# LazeMWC.net
KiCad netlist of a schematic drawn in Altium Designer
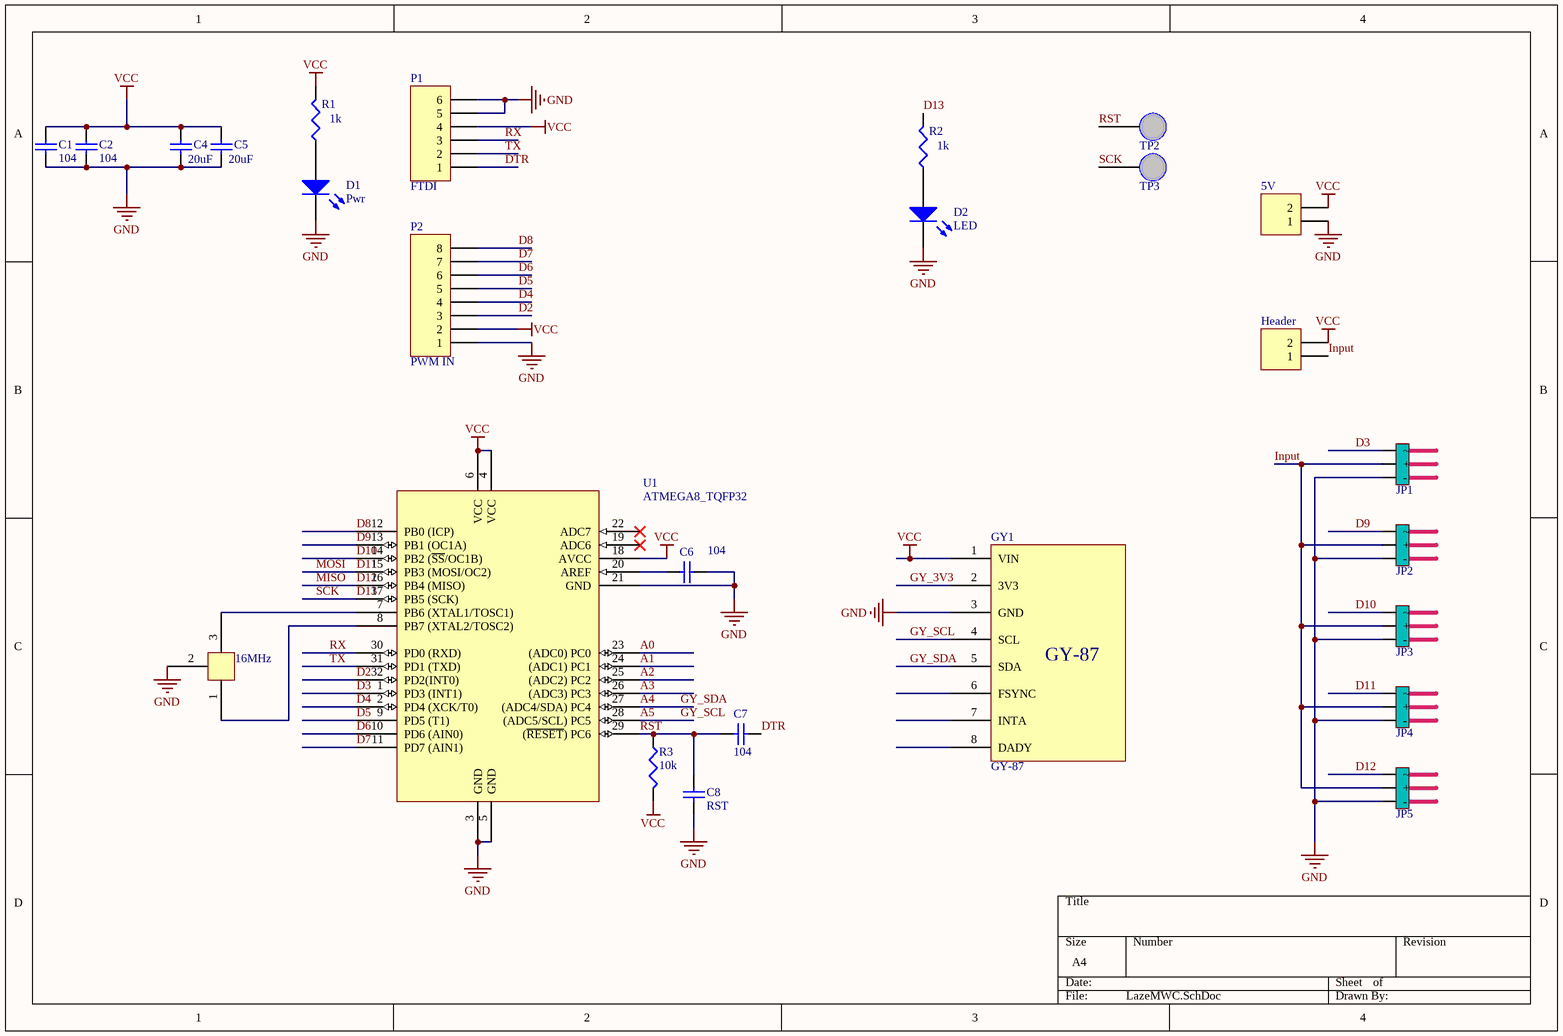
[diagram p0: LazeMWC.SchDoc]

(export (version "E")
  (design (tool "Eeschema 10.0.6"))
  (components
    (comp (ref "5V")
      (value "Header 2")
      (footprint "HDR1X2")
      (description "Header, 2-Pin")
      (fields (field (name "PUBLISHER") "Altium Limited"))
      (libsource (lib "Miscellaneous Connectors") (part "Header 2"))
    )
    (comp (ref "C1")
      (value "104")
      (footprint "CAPC1608L")
      (description "Capacitor (Semiconductor SIM Model)")
      (fields (field (name "PUBLISHER") "Altium Limited"))
      (libsource (lib "Miscellaneous Devices") (part "Cap Semi"))
    )
    (comp (ref "C2")
      (value "104")
      (footprint "CAPC1608L")
      (description "Capacitor (Semiconductor SIM Model)")
      (fields (field (name "PUBLISHER") "Altium Limited"))
      (libsource (lib "Miscellaneous Devices") (part "Cap Semi"))
    )
    (comp (ref "C4")
      (value "20uF")
      (footprint "CAPC3216L")
      (description "Capacitor (Semiconductor SIM Model)")
      (fields (field (name "PUBLISHER") "Altium Limited"))
      (libsource (lib "Miscellaneous Devices") (part "Cap Semi"))
    )
    (comp (ref "C5")
      (value "20uF")
      (footprint "CAPC3216L")
      (description "Capacitor (Semiconductor SIM Model)")
      (fields (field (name "PUBLISHER") "Altium Limited"))
      (libsource (lib "Miscellaneous Devices") (part "Cap Semi"))
    )
    (comp (ref "C6")
      (value "104")
      (footprint "CAPC1608L")
      (description "Capacitor (Semiconductor SIM Model)")
      (fields (field (name "PUBLISHER") "Altium Limited"))
      (libsource (lib "Miscellaneous Devices") (part "Cap Semi"))
    )
    (comp (ref "C7")
      (value "104")
      (footprint "CAPC1608L")
      (description "Capacitor (Semiconductor SIM Model)")
      (fields (field (name "PUBLISHER") "Altium Limited"))
      (libsource (lib "Miscellaneous Devices") (part "Cap Semi"))
    )
    (comp (ref "C8")
      (value "RST")
      (footprint "CAPC1608L")
      (description "Capacitor (Semiconductor SIM Model)")
      (fields (field (name "PUBLISHER") "Altium Limited"))
      (libsource (lib "Miscellaneous Devices") (part "Cap Semi"))
    )
    (comp (ref "Crystal1")
      (value "16MHz")
      (footprint "Crystal3Foot")
      (libsource (lib "Drone") (part "Crystal3Foot"))
    )
    (comp (ref "D1")
      (value "Pwr")
      (footprint "CAPC2012L")
      (description "Typical RED, GREEN, YELLOW, AMBER GaAs LED")
      (fields (field (name "PUBLISHER") "Altium Limited"))
      (libsource (lib "Miscellaneous Devices") (part "LED2"))
    )
    (comp (ref "D2")
      (value "LED")
      (footprint "CAPC2012L")
      (description "Typical RED, GREEN, YELLOW, AMBER GaAs LED")
      (fields (field (name "PUBLISHER") "Altium Limited"))
      (libsource (lib "Miscellaneous Devices") (part "LED2"))
    )
    (comp (ref "GY1") (value "GY-87") (footprint "GY-87") (libsource (lib "Drone") (part "GY-87")))
    (comp (ref "Header")
      (value "Header 2")
      (footprint "HDR1X2")
      (description "Header, 2-Pin")
      (fields (field (name "PUBLISHER") "Altium Limited"))
      (libsource (lib "Miscellaneous Connectors") (part "Header 2"))
    )
    (comp (ref "JP1")
      (value "Servo out 1")
      (footprint "JP")
      (description "Header, 3-Pin, 0.1\"")
      (fields (field (name "MANUFACTURER") "Generic Components"))
      (libsource (lib "Drone") (part "Hdr 3 Pin 0.1"))
    )
    (comp (ref "JP2")
      (value "Servo out 1")
      (footprint "JP")
      (description "Header, 3-Pin, 0.1\"")
      (fields (field (name "MANUFACTURER") "Generic Components"))
      (libsource (lib "Drone") (part "Hdr 3 Pin 0.1"))
    )
    (comp (ref "JP3")
      (value "Servo out 1")
      (footprint "JP")
      (description "Header, 3-Pin, 0.1\"")
      (fields (field (name "MANUFACTURER") "Generic Components"))
      (libsource (lib "Drone") (part "Hdr 3 Pin 0.1"))
    )
    (comp (ref "JP4")
      (value "Servo out 1")
      (footprint "JP")
      (description "Header, 3-Pin, 0.1\"")
      (fields (field (name "MANUFACTURER") "Generic Components"))
      (libsource (lib "Drone") (part "Hdr 3 Pin 0.1"))
    )
    (comp (ref "JP5")
      (value "Servo out 1")
      (footprint "JP")
      (description "Header, 3-Pin, 0.1\"")
      (fields (field (name "MANUFACTURER") "Generic Components"))
      (libsource (lib "Drone") (part "Hdr 3 Pin 0.1"))
    )
    (comp (ref "P1")
      (value "FTDI")
      (footprint "HDR1X6")
      (description "Header, 6-Pin")
      (fields (field (name "PUBLISHER") "Altium Limited"))
      (libsource (lib "Miscellaneous Connectors") (part "Header 6"))
    )
    (comp (ref "P2")
      (value "PWM IN")
      (footprint "HDR1X8")
      (description "Header, 8-Pin")
      (fields (field (name "PUBLISHER") "Altium Limited"))
      (libsource (lib "Miscellaneous Connectors") (part "Header 8"))
    )
    (comp (ref "R1")
      (value "1k")
      (footprint "RESC1608L")
      (description "Resistor")
      (fields (field (name "PUBLISHER") "Altium Limited"))
      (libsource (lib "Miscellaneous Devices") (part "Res3"))
    )
    (comp (ref "R2")
      (value "1k")
      (footprint "RESC1608L")
      (description "Resistor")
      (fields (field (name "PUBLISHER") "Altium Limited"))
      (libsource (lib "Miscellaneous Devices") (part "Res3"))
    )
    (comp (ref "R3")
      (value "10k")
      (footprint "RESC1608L")
      (description "Resistor")
      (fields (field (name "PUBLISHER") "Altium Limited"))
      (libsource (lib "Miscellaneous Devices") (part "Res3"))
    )
    (comp (ref "TP2") (value "Test Pad") (footprint "Test Pad") (libsource (lib "Drone") (part "Test Pad")))
    (comp (ref "TP3") (value "Test Pad") (footprint "Test Pad") (libsource (lib "Drone") (part "Test Pad")))
    (comp (ref "U1")
      (value "ATMEGA8_TQFP32")
      (footprint "atmega328fix")
      (description "Atmel Microcontroller - Library created by carel..  <www.mpfreezone.com>")
      (libsource (lib "Drone") (part "ATMEGA8_TQFP32"))
    )
  )
  (nets
    (net (code "1") (name "/A0") (class "Default")
      (node (ref "U1") (pin "23") (pinfunction "(ADC0)_PC0_23") (pintype "bidirectional"))
    )
    (net (code "2") (name "/A1") (class "Default")
      (node (ref "U1") (pin "24") (pinfunction "(ADC1)_PC1_24") (pintype "bidirectional"))
    )
    (net (code "3") (name "/A2") (class "Default")
      (node (ref "U1") (pin "25") (pinfunction "(ADC2)_PC2_25") (pintype "bidirectional"))
    )
    (net (code "4") (name "/A3") (class "Default")
      (node (ref "U1") (pin "26") (pinfunction "(ADC3)_PC3_26") (pintype "bidirectional"))
    )
    (net (code "5") (name "/A4") (class "Default")
      (node (ref "GY1") (pin "5") (pinfunction "SDA_5") (pintype "passive"))
      (node (ref "U1") (pin "27") (pinfunction "(ADC4/SDA)_PC4_27") (pintype "bidirectional"))
    )
    (net (code "6") (name "/A5") (class "Default")
      (node (ref "GY1") (pin "4") (pinfunction "SCL_4") (pintype "passive"))
      (node (ref "U1") (pin "28") (pinfunction "(ADC5/SCL)_PC5_28") (pintype "bidirectional"))
    )
    (net (code "7") (name "/D2") (class "Default")
      (node (ref "P2") (pin "3") (pinfunction "3_3") (pintype "passive"))
      (node (ref "U1") (pin "32") (pinfunction "PD2(INT0)_32") (pintype "bidirectional"))
    )
    (net (code "8") (name "/D3") (class "Default")
      (node (ref "JP1") (pin "1") (pinfunction "~_1") (pintype "passive"))
      (node (ref "U1") (pin "1") (pinfunction "PD3_(INT1)_1") (pintype "bidirectional"))
    )
    (net (code "9") (name "/D4") (class "Default")
      (node (ref "P2") (pin "4") (pinfunction "4_4") (pintype "passive"))
      (node (ref "U1") (pin "2") (pinfunction "PD4_(XCK/T0)_2") (pintype "bidirectional"))
    )
    (net (code "10") (name "/D5") (class "Default")
      (node (ref "P2") (pin "5") (pinfunction "5_5") (pintype "passive"))
      (node (ref "U1") (pin "9") (pinfunction "PD5_(T1)_9") (pintype "passive"))
    )
    (net (code "11") (name "/D6") (class "Default")
      (node (ref "P2") (pin "6") (pinfunction "6_6") (pintype "passive"))
      (node (ref "U1") (pin "10") (pinfunction "PD6_(AIN0)_10") (pintype "passive"))
    )
    (net (code "12") (name "/D7") (class "Default")
      (node (ref "P2") (pin "7") (pinfunction "7_7") (pintype "passive"))
      (node (ref "U1") (pin "11") (pinfunction "PD7_(AIN1)_11") (pintype "passive"))
    )
    (net (code "13") (name "/D8") (class "Default")
      (node (ref "P2") (pin "8") (pinfunction "8_8") (pintype "passive"))
      (node (ref "U1") (pin "12") (pinfunction "PB0_(ICP)_12") (pintype "passive"))
    )
    (net (code "14") (name "/D9") (class "Default")
      (node (ref "JP2") (pin "1") (pinfunction "~_1") (pintype "passive"))
      (node (ref "U1") (pin "13") (pinfunction "PB1_(OC1A)_13") (pintype "bidirectional"))
    )
    (net (code "15") (name "/D10") (class "Default")
      (node (ref "JP3") (pin "1") (pinfunction "~_1") (pintype "passive"))
      (node (ref "U1") (pin "14") (pinfunction "PB2_(~{SS}/OC1B)_14") (pintype "bidirectional"))
    )
    (net (code "16") (name "/D11") (class "Default")
      (node (ref "JP4") (pin "1") (pinfunction "~_1") (pintype "passive"))
      (node (ref "U1") (pin "15") (pinfunction "PB3_(MOSI/OC2)_15") (pintype "bidirectional"))
    )
    (net (code "17") (name "/D12") (class "Default")
      (node (ref "JP5") (pin "1") (pinfunction "~_1") (pintype "passive"))
      (node (ref "U1") (pin "16") (pinfunction "PB4_(MISO)_16") (pintype "bidirectional"))
    )
    (net (code "18") (name "/D13") (class "Default")
      (node (ref "R2") (pin "2") (pinfunction "2_2") (pintype "passive"))
      (node (ref "TP3") (pin "1") (pinfunction "1_1") (pintype "passive"))
      (node (ref "U1") (pin "17") (pinfunction "PB5_(SCK)_17") (pintype "bidirectional"))
    )
    (net (code "19") (name "/DTR") (class "Default")
      (node (ref "C7") (pin "2") (pinfunction "2_2") (pintype "passive"))
      (node (ref "P1") (pin "1") (pinfunction "1_1") (pintype "passive"))
    )
    (net (code "20") (name "/GY_3V3") (class "Default")
      (node (ref "GY1") (pin "2") (pinfunction "3V3_2") (pintype "passive"))
    )
    (net (code "21") (name "/Input") (class "Default")
      (node (ref "Header") (pin "1") (pinfunction "1_1") (pintype "passive"))
      (node (ref "JP1") (pin "2") (pinfunction "+_2") (pintype "passive"))
      (node (ref "JP2") (pin "2") (pinfunction "+_2") (pintype "passive"))
      (node (ref "JP3") (pin "2") (pinfunction "+_2") (pintype "passive"))
      (node (ref "JP4") (pin "2") (pinfunction "+_2") (pintype "passive"))
      (node (ref "JP5") (pin "2") (pinfunction "+_2") (pintype "passive"))
    )
    (net (code "22") (name "/RST") (class "Default")
      (node (ref "C7") (pin "1") (pinfunction "1_1") (pintype "passive"))
      (node (ref "C8") (pin "2") (pinfunction "2_2") (pintype "passive"))
      (node (ref "R3") (pin "1") (pinfunction "1_1") (pintype "passive"))
      (node (ref "TP2") (pin "1") (pinfunction "1_1") (pintype "passive"))
      (node (ref "U1") (pin "29") (pinfunction "(~{RESET})_PC6_29") (pintype "bidirectional"))
    )
    (net (code "23") (name "/RX") (class "Default")
      (node (ref "P1") (pin "3") (pinfunction "3_3") (pintype "passive"))
      (node (ref "U1") (pin "30") (pinfunction "PD0_(RXD)_30") (pintype "bidirectional"))
    )
    (net (code "24") (name "/TX") (class "Default")
      (node (ref "P1") (pin "2") (pinfunction "2_2") (pintype "passive"))
      (node (ref "U1") (pin "31") (pinfunction "PD1_(TXD)_31") (pintype "bidirectional"))
    )
    (net (code "25") (name "GND") (class "Default")
      (node (ref "5V") (pin "1") (pinfunction "1_1") (pintype "passive"))
      (node (ref "C1") (pin "1") (pinfunction "1_1") (pintype "passive"))
      (node (ref "C2") (pin "1") (pinfunction "1_1") (pintype "passive"))
      (node (ref "C4") (pin "1") (pinfunction "1_1") (pintype "passive"))
      (node (ref "C5") (pin "1") (pinfunction "1_1") (pintype "passive"))
      (node (ref "C6") (pin "2") (pinfunction "2_2") (pintype "passive"))
      (node (ref "C8") (pin "1") (pinfunction "1_1") (pintype "passive"))
      (node (ref "Crystal1") (pin "2") (pinfunction "2_2") (pintype "passive"))
      (node (ref "D1") (pin "2") (pinfunction "K_2") (pintype "passive"))
      (node (ref "D2") (pin "2") (pinfunction "K_2") (pintype "passive"))
      (node (ref "GY1") (pin "3") (pinfunction "GND_3") (pintype "passive"))
      (node (ref "JP1") (pin "3") (pinfunction "-_3") (pintype "passive"))
      (node (ref "JP2") (pin "3") (pinfunction "-_3") (pintype "passive"))
      (node (ref "JP3") (pin "3") (pinfunction "-_3") (pintype "passive"))
      (node (ref "JP4") (pin "3") (pinfunction "-_3") (pintype "passive"))
      (node (ref "JP5") (pin "3") (pinfunction "-_3") (pintype "passive"))
      (node (ref "P1") (pin "5") (pinfunction "5_5") (pintype "passive"))
      (node (ref "P1") (pin "6") (pinfunction "6_6") (pintype "passive"))
      (node (ref "P2") (pin "1") (pinfunction "1_1") (pintype "passive"))
      (node (ref "U1") (pin "21") (pinfunction "GND_21") (pintype "passive"))
      (node (ref "U1") (pin "3") (pinfunction "GND_3") (pintype "passive"))
      (node (ref "U1") (pin "5") (pinfunction "GND_5") (pintype "power_in"))
    )
    (net (code "26") (name "Net-(Crystal1-0)") (class "Default")
      (node (ref "Crystal1") (pin "1") (pinfunction "0_1") (pintype "passive"))
      (node (ref "U1") (pin "8") (pinfunction "PB7_(XTAL2/TOSC2)_8") (pintype "passive"))
    )
    (net (code "27") (name "Net-(Crystal1-1)") (class "Default")
      (node (ref "Crystal1") (pin "3") (pinfunction "1_3") (pintype "passive"))
      (node (ref "U1") (pin "7") (pinfunction "PB6_(XTAL1/TOSC1)_7") (pintype "passive"))
    )
    (net (code "28") (name "Net-(D1-A)") (class "Default")
      (node (ref "D1") (pin "1") (pinfunction "A_1") (pintype "passive"))
      (node (ref "R1") (pin "1") (pinfunction "1_1") (pintype "passive"))
    )
    (net (code "29") (name "Net-(D2-A)") (class "Default")
      (node (ref "D2") (pin "1") (pinfunction "A_1") (pintype "passive"))
      (node (ref "R2") (pin "1") (pinfunction "1_1") (pintype "passive"))
    )
    (net (code "30") (name "Net-(U1-AREF)") (class "Default")
      (node (ref "C6") (pin "1") (pinfunction "1_1") (pintype "passive"))
      (node (ref "U1") (pin "20") (pinfunction "AREF_20") (pintype "input"))
    )
    (net (code "31") (name "VCC") (class "Default")
      (node (ref "5V") (pin "2") (pinfunction "2_2") (pintype "passive"))
      (node (ref "C1") (pin "2") (pinfunction "2_2") (pintype "passive"))
      (node (ref "C2") (pin "2") (pinfunction "2_2") (pintype "passive"))
      (node (ref "C4") (pin "2") (pinfunction "2_2") (pintype "passive"))
      (node (ref "C5") (pin "2") (pinfunction "2_2") (pintype "passive"))
      (node (ref "GY1") (pin "1") (pinfunction "VIN_1") (pintype "passive"))
      (node (ref "Header") (pin "2") (pinfunction "2_2") (pintype "passive"))
      (node (ref "P1") (pin "4") (pinfunction "4_4") (pintype "passive"))
      (node (ref "P2") (pin "2") (pinfunction "2_2") (pintype "passive"))
      (node (ref "R1") (pin "2") (pinfunction "2_2") (pintype "passive"))
      (node (ref "R3") (pin "2") (pinfunction "2_2") (pintype "passive"))
      (node (ref "U1") (pin "18") (pinfunction "AVCC_18") (pintype "passive"))
      (node (ref "U1") (pin "4") (pinfunction "VCC_4") (pintype "power_in"))
      (node (ref "U1") (pin "6") (pinfunction "VCC_6") (pintype "passive"))
    )
    (net (code "32") (name "unconnected-(GY1-DADY-Pad8)") (class "Default")
      (node (ref "GY1") (pin "8") (pinfunction "DADY_8") (pintype "passive"))
    )
    (net (code "33") (name "unconnected-(GY1-FSYNC-Pad6)") (class "Default")
      (node (ref "GY1") (pin "6") (pinfunction "FSYNC_6") (pintype "passive"))
    )
    (net (code "34") (name "unconnected-(GY1-INTA-Pad7)") (class "Default")
      (node (ref "GY1") (pin "7") (pinfunction "INTA_7") (pintype "passive"))
    )
    (net (code "35") (name "unconnected-(U1-ADC6-Pad19)") (class "Default")
      (node (ref "U1") (pin "19") (pinfunction "ADC6_19") (pintype "input+no_connect"))
    )
    (net (code "36") (name "unconnected-(U1-ADC7-Pad22)") (class "Default")
      (node (ref "U1") (pin "22") (pinfunction "ADC7_22") (pintype "input+no_connect"))
    )
  )
)
